# Power_12V_to_servo.net
KiCad netlist of a schematic drawn in Altium Designer
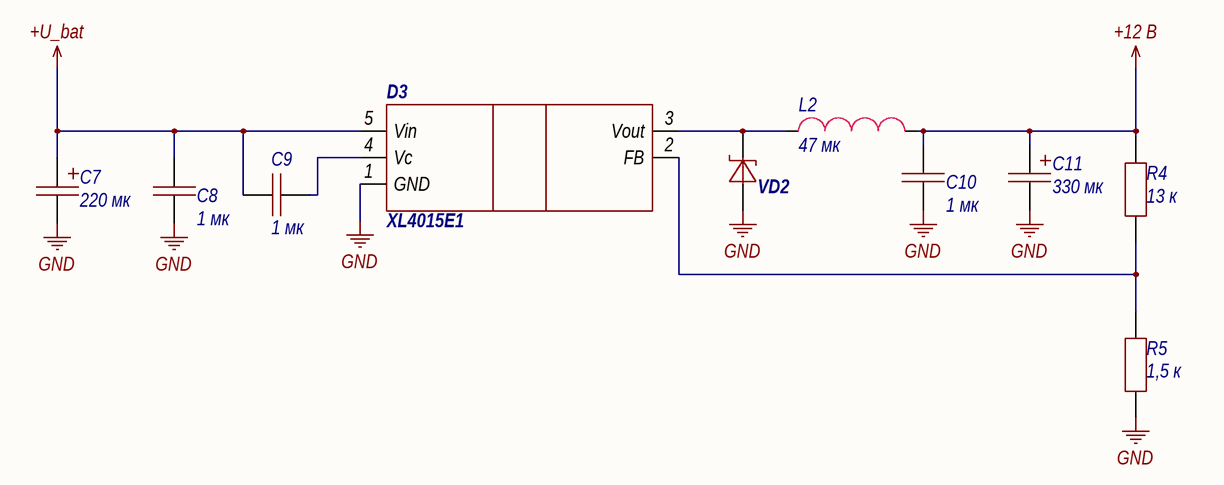
[diagram p0: Power 12V to servo.SchDoc]

(export (version "E")
  (design (tool "Eeschema 10.0.6"))
  (components
    (comp (ref "C7")
      (value "220 мк")
      (footprint "RADIAL-2 10MM")
      (description "Конденсатор электролит. 220 мкФ, 50 В, 10мм")
      (fields (field (name "Comment") "Конденсатор полевой"))
      (libsource (lib "PionerSCHLibrary") (part "Capacitor_pol"))
    )
    (comp (ref "C8")
      (value "1 мк")
      (footprint "0603C")
      (description "Конденсатор керамический SMD, 1 мкФ, 0603")
      (fields (field (name "Comment") "Конденсатор"))
      (libsource (lib "PionerSCHLibrary") (part "Capacitor"))
    )
    (comp (ref "C9")
      (value "1 мк")
      (footprint "0603C")
      (description "Конденсатор керамический SMD, 1 мкФ, 0603")
      (fields (field (name "Comment") "Конденсатор"))
      (libsource (lib "PionerSCHLibrary") (part "Capacitor"))
    )
    (comp (ref "C10")
      (value "1 мк")
      (footprint "0603C")
      (description "Конденсатор керамический SMD, 1 мкФ, 0603")
      (fields (field (name "Comment") "Конденсатор"))
      (libsource (lib "PionerSCHLibrary") (part "Capacitor"))
    )
    (comp (ref "C11")
      (value "330 мк")
      (footprint "RADIAL-2 10MM")
      (description "Конденсатор электролит. 330 мкФ, 25 В, 10 мм")
      (fields (field (name "Comment") "Конденсатор полевой"))
      (libsource (lib "PionerSCHLibrary") (part "Capacitor_pol"))
    )
    (comp (ref "D3")
      (value "XL4015E1")
      (footprint "TO-263-5")
      (description "Импульсный DC-DC преобразователь. Вход до 36 В. Регулируемый выход. Выходной ток до 5А.")
      (libsource (lib "PionerSCHLibrary") (part "XL4015E1"))
    )
    (comp (ref "L2")
      (value "47 мк")
      (footprint "IHLP-6767")
      (description "Индуктивность экранированная 47 мкГн, 20%, 8.7 А, 42.7 мОм, IHLP6767GZER470M11")
      (fields (field (name "Comment") "Inductance"))
      (libsource (lib "PionerSCHLibrary") (part "Inductance"))
    )
    (comp (ref "R4")
      (value "13 к")
      (footprint "0603R")
      (description "Резистор SMD, 0603, 13 кОм")
      (fields (field (name "Comment") "Resistor"))
      (libsource (lib "PionerSCHLibrary") (part "Resistor"))
    )
    (comp (ref "R5")
      (value "1,5 к")
      (footprint "0603R")
      (description "Резистор SMD 0603, 1.5 кОм")
      (fields (field (name "Comment") "Resistor"))
      (libsource (lib "PionerSCHLibrary") (part "Resistor"))
    )
    (comp (ref "VD2")
      (value "Диод Шоттки")
      (footprint "SMC")
      (description "Диод Шоттки 40 В, 5 А, SMC, B540C-13-F")
      (libsource (lib "PionerSCHLibrary") (part "Schottky diode"))
    )
  )
  (nets
    (net (code "1") (name "+12 В") (class "Default")
      (node (ref "C10") (pin "1") (pinfunction "1_1") (pintype "passive"))
      (node (ref "C11") (pin "1") (pinfunction "1_1") (pintype "passive"))
      (node (ref "L2") (pin "2") (pinfunction "2_2") (pintype "passive"))
      (node (ref "R4") (pin "2") (pinfunction "2_2") (pintype "passive"))
    )
    (net (code "2") (name "+U_bat") (class "Default")
      (node (ref "C7") (pin "1") (pinfunction "1_1") (pintype "passive"))
      (node (ref "C8") (pin "2") (pinfunction "2_2") (pintype "passive"))
      (node (ref "C9") (pin "2") (pinfunction "2_2") (pintype "passive"))
      (node (ref "D3") (pin "5") (pinfunction "Vin_5") (pintype "passive"))
    )
    (net (code "3") (name "GND") (class "Default")
      (node (ref "C10") (pin "2") (pinfunction "2_2") (pintype "passive"))
      (node (ref "C11") (pin "2") (pinfunction "2_2") (pintype "passive"))
      (node (ref "C7") (pin "2") (pinfunction "2_2") (pintype "passive"))
      (node (ref "C8") (pin "1") (pinfunction "1_1") (pintype "passive"))
      (node (ref "D3") (pin "1") (pinfunction "GND_1") (pintype "passive"))
      (node (ref "R5") (pin "1") (pinfunction "1_1") (pintype "passive"))
      (node (ref "VD2") (pin "1") (pinfunction "1_1") (pintype "passive"))
    )
    (net (code "4") (name "Net-(D3-FB)") (class "Default")
      (node (ref "D3") (pin "2") (pinfunction "FB_2") (pintype "passive"))
      (node (ref "R4") (pin "1") (pinfunction "1_1") (pintype "passive"))
      (node (ref "R5") (pin "2") (pinfunction "2_2") (pintype "passive"))
    )
    (net (code "5") (name "Net-(D3-Vc)") (class "Default")
      (node (ref "C9") (pin "1") (pinfunction "1_1") (pintype "passive"))
      (node (ref "D3") (pin "4") (pinfunction "Vc_4") (pintype "passive"))
    )
    (net (code "6") (name "Net-(D3-Vout)") (class "Default")
      (node (ref "D3") (pin "3") (pinfunction "Vout_3") (pintype "passive"))
      (node (ref "L2") (pin "1") (pinfunction "1_1") (pintype "passive"))
      (node (ref "VD2") (pin "2") (pinfunction "2_2") (pintype "passive"))
    )
  )
)
